# SENSE.net
KiCad netlist of a schematic drawn in Altium Designer
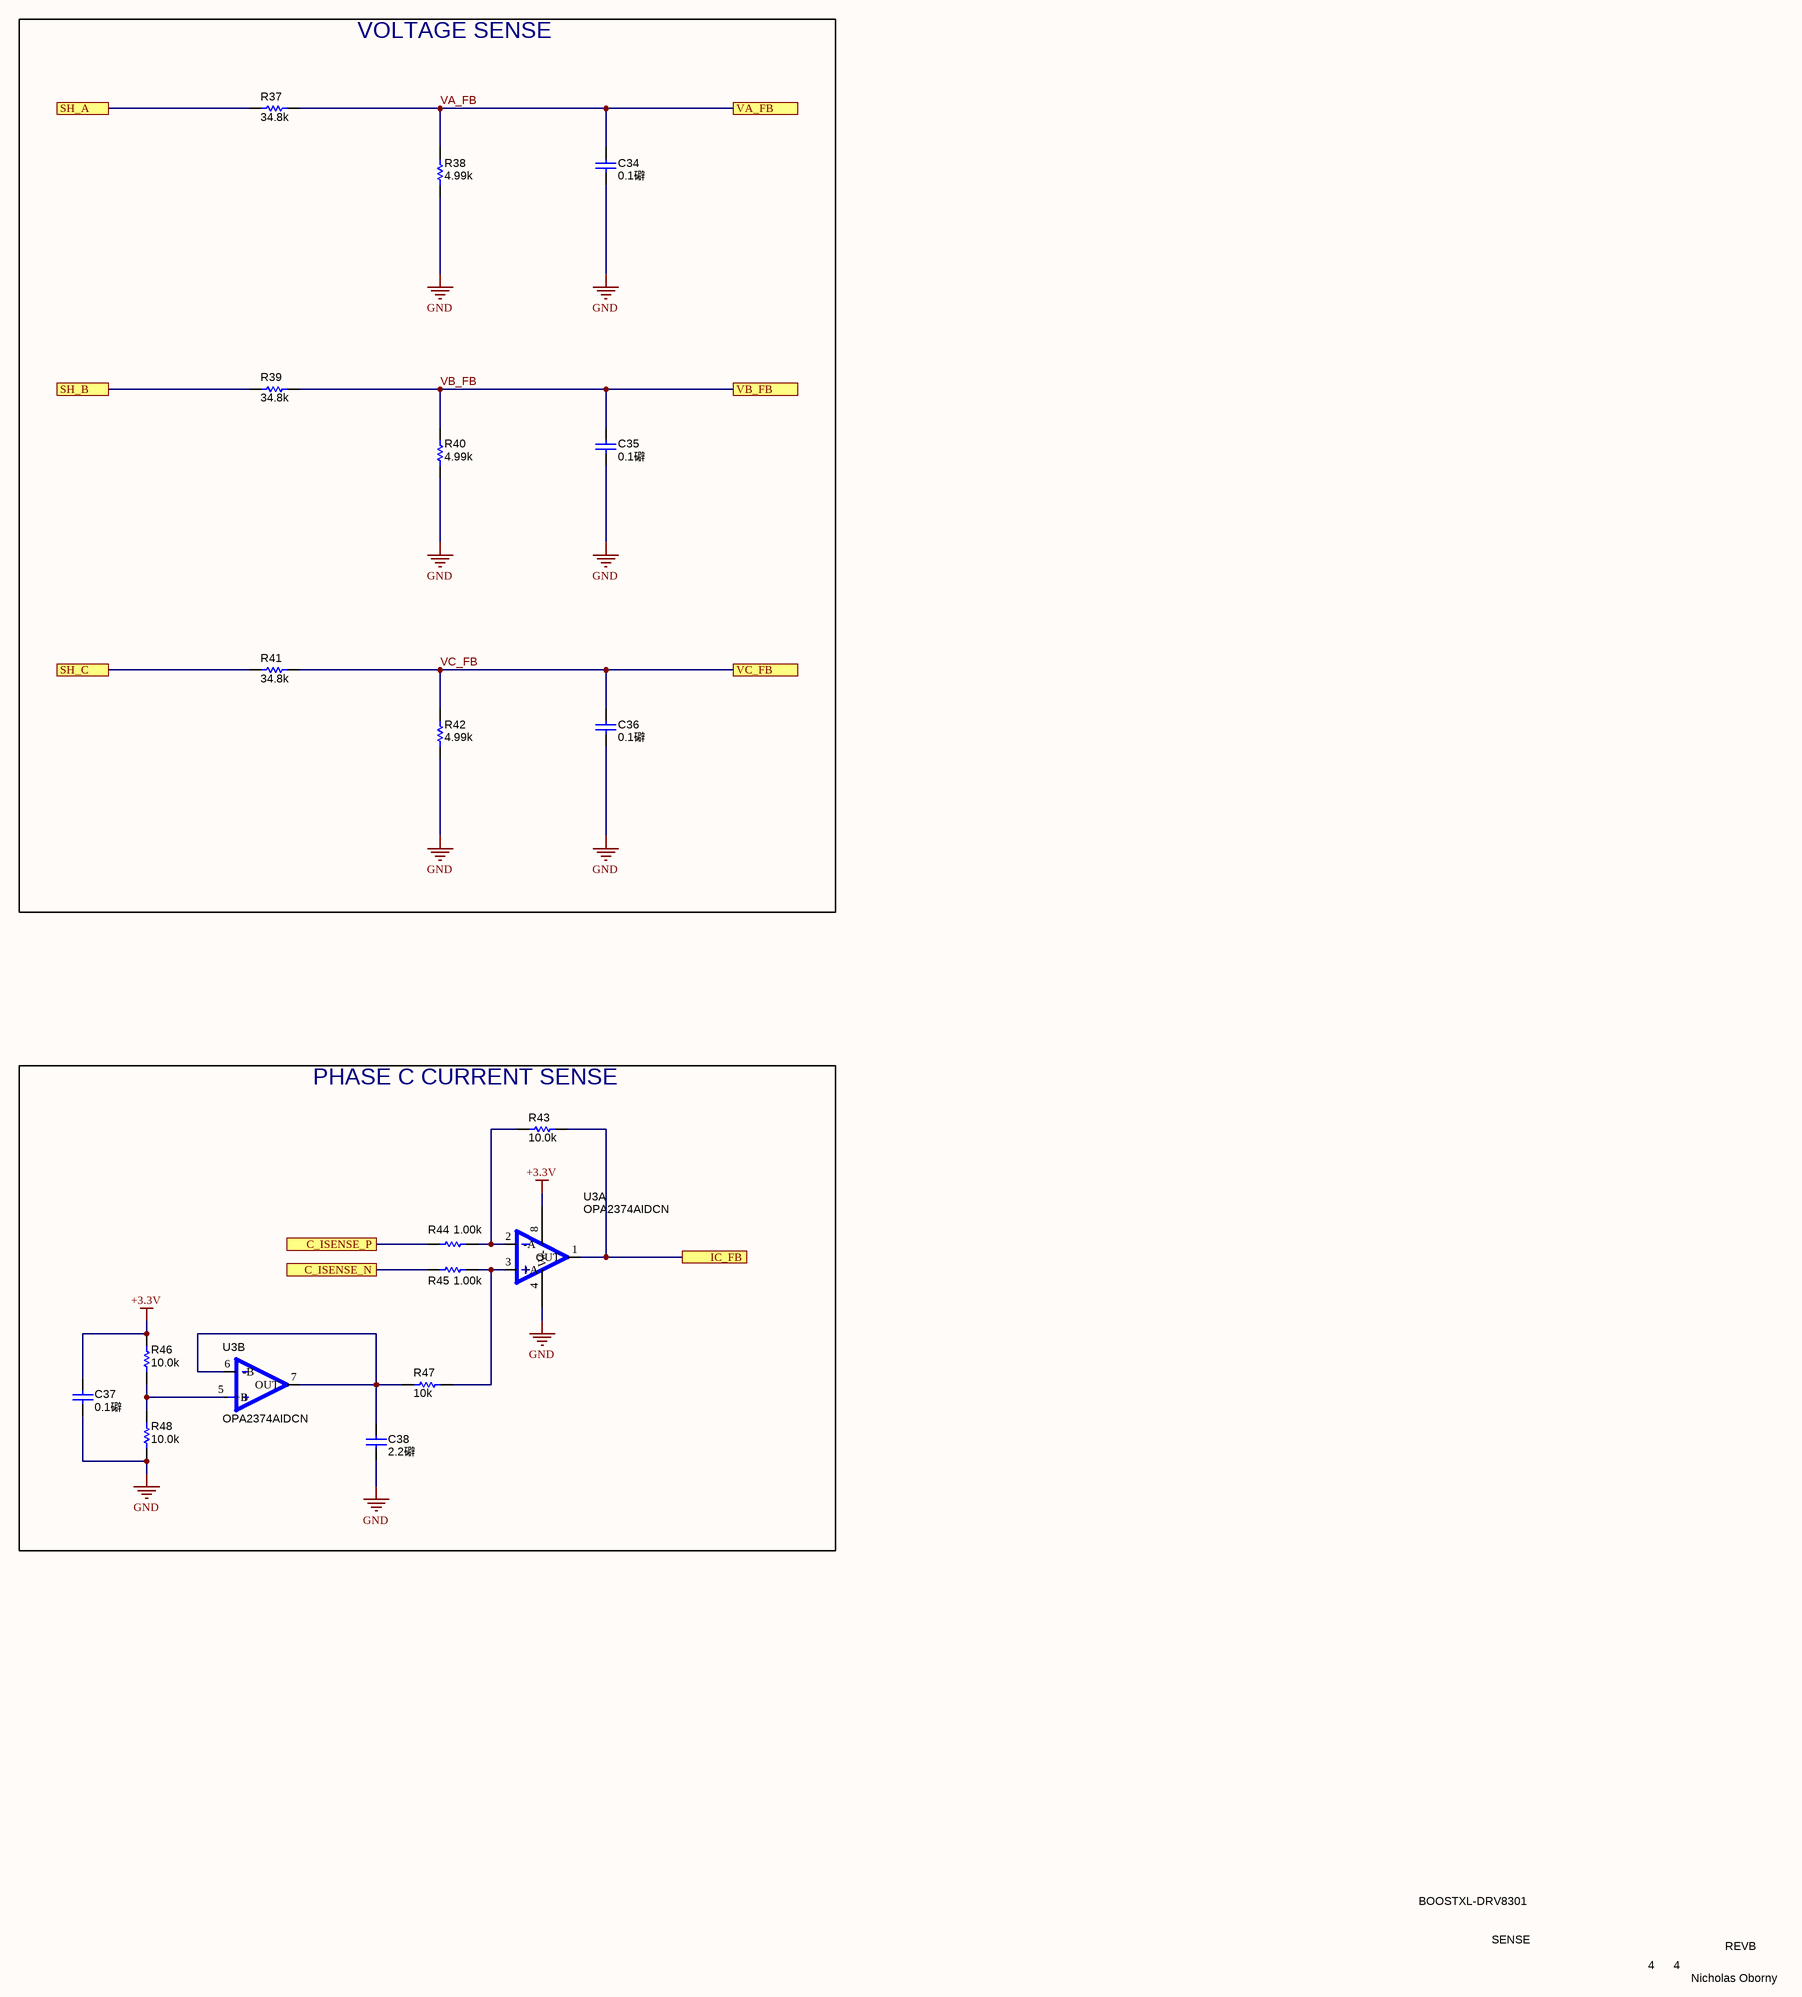
[diagram p0: SENSE.SchDoc]

(export (version "E")
  (design (tool "Eeschema 10.0.6"))
  (components
    (comp (ref "C34")
      (value "C0603C104J4RACTU")
      (footprint "0603L")
      (description "CAP, CERM, 0.1uF, 16V, +/-5%, X7R, 0603")
      (fields
        (field (name "VALUEDISPLAYED") "0.1礔")
        (field (name "MANUFACTURER") "Kemet")
        (field (name "PUBLISHER") "Texas Instruments")
      )
      (libsource (lib "Capacitor_Ceramic") (part "C0603C104J4RACTU"))
    )
    (comp (ref "C35")
      (value "C0603C104J4RACTU")
      (footprint "0603L")
      (description "CAP, CERM, 0.1uF, 16V, +/-5%, X7R, 0603")
      (fields
        (field (name "VALUEDISPLAYED") "0.1礔")
        (field (name "MANUFACTURER") "Kemet")
        (field (name "PUBLISHER") "Texas Instruments")
      )
      (libsource (lib "Capacitor_Ceramic") (part "C0603C104J4RACTU"))
    )
    (comp (ref "C36")
      (value "C0603C104J4RACTU")
      (footprint "0603L")
      (description "CAP, CERM, 0.1uF, 16V, +/-5%, X7R, 0603")
      (fields
        (field (name "VALUEDISPLAYED") "0.1礔")
        (field (name "MANUFACTURER") "Kemet")
        (field (name "PUBLISHER") "Texas Instruments")
      )
      (libsource (lib "Capacitor_Ceramic") (part "C0603C104J4RACTU"))
    )
    (comp (ref "C37")
      (value "C0603C104J4RACTU")
      (footprint "0603L")
      (description "CAP, CERM, 0.1uF, 16V, +/-5%, X7R, 0603")
      (fields
        (field (name "VALUEDISPLAYED") "0.1礔")
        (field (name "MANUFACTURER") "Kemet")
        (field (name "PUBLISHER") "Texas Instruments")
      )
      (libsource (lib "Capacitor_Ceramic") (part "C0603C104J4RACTU"))
    )
    (comp (ref "C38")
      (value "C0603C225M8PACTU")
      (footprint "0603L")
      (description "CAP, CERM, 2.2uF, 10V, +/-20%, X5R, 0603")
      (fields
        (field (name "VALUEDISPLAYED") "2.2礔")
        (field (name "MANUFACTURER") "Kemet")
        (field (name "PUBLISHER") "Texas Instruments")
      )
      (libsource (lib "Capacitor_Ceramic") (part "C0603C225M8PACTU"))
    )
    (comp (ref "R37")
      (value "34.8k")
      (footprint "0603L")
      (description "RES, 34.8k ohm, 1%, 0.1W, 0603")
      (fields
        (field (name "PARTNUMBER") "CRCW060334K8FKEA")
        (field (name "MANUFACTURER") "Vishay-Dale")
        (field (name "PUBLISHER") "Texas Instruments")
      )
      (libsource (lib "Resistor_0603") (part "CRCW060334K8FKEA"))
    )
    (comp (ref "R38")
      (value "4.99k")
      (footprint "0603L")
      (description "RES, 4.99k ohm, 1%, 0.1W, 0603")
      (fields
        (field (name "PARTNUMBER") "CRCW06034K99FKEA")
        (field (name "MANUFACTURER") "Vishay-Dale")
        (field (name "PUBLISHER") "Texas Instruments")
      )
      (libsource (lib "Resistor_0603") (part "CRCW06034K99FKEA"))
    )
    (comp (ref "R39")
      (value "34.8k")
      (footprint "0603L")
      (description "RES, 34.8k ohm, 1%, 0.1W, 0603")
      (fields
        (field (name "PARTNUMBER") "CRCW060334K8FKEA")
        (field (name "MANUFACTURER") "Vishay-Dale")
        (field (name "PUBLISHER") "Texas Instruments")
      )
      (libsource (lib "Resistor_0603") (part "CRCW060334K8FKEA"))
    )
    (comp (ref "R40")
      (value "4.99k")
      (footprint "0603L")
      (description "RES, 4.99k ohm, 1%, 0.1W, 0603")
      (fields
        (field (name "PARTNUMBER") "CRCW06034K99FKEA")
        (field (name "MANUFACTURER") "Vishay-Dale")
        (field (name "PUBLISHER") "Texas Instruments")
      )
      (libsource (lib "Resistor_0603") (part "CRCW06034K99FKEA"))
    )
    (comp (ref "R41")
      (value "34.8k")
      (footprint "0603L")
      (description "RES, 34.8k ohm, 1%, 0.1W, 0603")
      (fields
        (field (name "PARTNUMBER") "CRCW060334K8FKEA")
        (field (name "MANUFACTURER") "Vishay-Dale")
        (field (name "PUBLISHER") "Texas Instruments")
      )
      (libsource (lib "Resistor_0603") (part "CRCW060334K8FKEA"))
    )
    (comp (ref "R42")
      (value "4.99k")
      (footprint "0603L")
      (description "RES, 4.99k ohm, 1%, 0.1W, 0603")
      (fields
        (field (name "PARTNUMBER") "CRCW06034K99FKEA")
        (field (name "MANUFACTURER") "Vishay-Dale")
        (field (name "PUBLISHER") "Texas Instruments")
      )
      (libsource (lib "Resistor_0603") (part "CRCW06034K99FKEA"))
    )
    (comp (ref "R43")
      (value "10.0k")
      (footprint "0603L")
      (description "RES, 10.0k ohm, 0.1%, 0.1W, 0603")
      (fields
        (field (name "PARTNUMBER") "RG1608P-103-B-T5")
        (field (name "MANUFACTURER") "Susumu Co Ltd")
        (field (name "PUBLISHER") "Texas Instruments")
      )
      (libsource (lib "Resistor_0603") (part "RG1608P-103-B-T5"))
    )
    (comp (ref "R44")
      (value "1.00k")
      (footprint "0603L")
      (description "RES, 1.00k ohm, 1%, 0.1W, 0603")
      (fields
        (field (name "PARTNUMBER") "CRCW06031K00FKEA")
        (field (name "MANUFACTURER") "Vishay-Dale")
        (field (name "PUBLISHER") "Texas Instruments")
      )
      (libsource (lib "Resistor_0603") (part "CRCW06031K00FKEA"))
    )
    (comp (ref "R45")
      (value "1.00k")
      (footprint "0603L")
      (description "RES, 1.00k ohm, 1%, 0.1W, 0603")
      (fields
        (field (name "PARTNUMBER") "CRCW06031K00FKEA")
        (field (name "MANUFACTURER") "Vishay-Dale")
        (field (name "PUBLISHER") "Texas Instruments")
      )
      (libsource (lib "Resistor_0603") (part "CRCW06031K00FKEA"))
    )
    (comp (ref "R46")
      (value "10.0k")
      (footprint "0603L")
      (description "RES, 10.0k ohm, 0.1%, 0.1W, 0603")
      (fields
        (field (name "PARTNUMBER") "RG1608P-103-B-T5")
        (field (name "MANUFACTURER") "Susumu Co Ltd")
        (field (name "PUBLISHER") "Texas Instruments")
      )
      (libsource (lib "Resistor_0603") (part "RG1608P-103-B-T5"))
    )
    (comp (ref "R47")
      (value "10k")
      (footprint "0603L")
      (description "RES, 10k ohm, 5%, 0.1W, 0603")
      (fields
        (field (name "PARTNUMBER") "CRCW060310K0JNEA")
        (field (name "MANUFACTURER") "Vishay-Dale")
        (field (name "PUBLISHER") "Texas Instruments")
      )
      (libsource (lib "Resistor_0603") (part "CRCW060310K0JNEA"))
    )
    (comp (ref "R48")
      (value "10.0k")
      (footprint "0603L")
      (description "RES, 10.0k ohm, 0.1%, 0.1W, 0603")
      (fields
        (field (name "PARTNUMBER") "RG1608P-103-B-T5")
        (field (name "MANUFACTURER") "Susumu Co Ltd")
        (field (name "PUBLISHER") "Texas Instruments")
      )
      (libsource (lib "Resistor_0603") (part "RG1608P-103-B-T5"))
    )
    (comp (ref "U3")
      (value "OPA2374AIDCN")
      (footprint "DCN")
      (description "IC, CMOS, R-R I/O  Op Amp, Single Supply, 6.5MHz, 585uA")
      (fields (field (name "MANUFACTURER") "TI"))
      (libsource (lib "PADSlegacy_Active") (part "OPA2374AIDCN"))
    )
  )
  (nets
    (net (code "1") (name "+3.3V") (class "Default")
      (node (ref "C37") (pin "1") (pinfunction "1_1") (pintype "passive"))
      (node (ref "R46") (pin "2") (pinfunction "2_2") (pintype "passive"))
      (node (ref "U3") (pin "8") (pinfunction "V+_8") (pintype "passive"))
    )
    (net (code "2") (name "/C_ISENSE_N") (class "Default")
      (node (ref "R45") (pin "1") (pinfunction "1_1") (pintype "passive"))
    )
    (net (code "3") (name "/C_ISENSE_P") (class "Default")
      (node (ref "R44") (pin "1") (pinfunction "1_1") (pintype "passive"))
    )
    (net (code "4") (name "/IC_FB") (class "Default")
      (node (ref "R43") (pin "2") (pinfunction "2_2") (pintype "passive"))
      (node (ref "U3") (pin "1") (pinfunction "OUT_1") (pintype "passive"))
    )
    (net (code "5") (name "/SH_A") (class "Default")
      (node (ref "R37") (pin "1") (pinfunction "1_1") (pintype "passive"))
    )
    (net (code "6") (name "/SH_B") (class "Default")
      (node (ref "R39") (pin "1") (pinfunction "1_1") (pintype "passive"))
    )
    (net (code "7") (name "/SH_C") (class "Default")
      (node (ref "R41") (pin "1") (pinfunction "1_1") (pintype "passive"))
    )
    (net (code "8") (name "/VA_FB") (class "Default")
      (node (ref "C34") (pin "1") (pinfunction "1_1") (pintype "passive"))
      (node (ref "R37") (pin "2") (pinfunction "2_2") (pintype "passive"))
      (node (ref "R38") (pin "2") (pinfunction "2_2") (pintype "passive"))
    )
    (net (code "9") (name "/VB_FB") (class "Default")
      (node (ref "C35") (pin "1") (pinfunction "1_1") (pintype "passive"))
      (node (ref "R39") (pin "2") (pinfunction "2_2") (pintype "passive"))
      (node (ref "R40") (pin "2") (pinfunction "2_2") (pintype "passive"))
    )
    (net (code "10") (name "/VC_FB") (class "Default")
      (node (ref "C36") (pin "1") (pinfunction "1_1") (pintype "passive"))
      (node (ref "R41") (pin "2") (pinfunction "2_2") (pintype "passive"))
      (node (ref "R42") (pin "2") (pinfunction "2_2") (pintype "passive"))
    )
    (net (code "11") (name "GND") (class "Default")
      (node (ref "C34") (pin "2") (pinfunction "2_2") (pintype "passive"))
      (node (ref "C35") (pin "2") (pinfunction "2_2") (pintype "passive"))
      (node (ref "C36") (pin "2") (pinfunction "2_2") (pintype "passive"))
      (node (ref "C37") (pin "2") (pinfunction "2_2") (pintype "passive"))
      (node (ref "C38") (pin "2") (pinfunction "2_2") (pintype "passive"))
      (node (ref "R38") (pin "1") (pinfunction "1_1") (pintype "passive"))
      (node (ref "R40") (pin "1") (pinfunction "1_1") (pintype "passive"))
      (node (ref "R42") (pin "1") (pinfunction "1_1") (pintype "passive"))
      (node (ref "R48") (pin "1") (pinfunction "1_1") (pintype "passive"))
      (node (ref "U3") (pin "4") (pinfunction "V-_4") (pintype "passive"))
    )
    (net (code "12") (name "Net-(U3A-+A)") (class "Default")
      (node (ref "R45") (pin "2") (pinfunction "2_2") (pintype "passive"))
      (node (ref "R47") (pin "2") (pinfunction "2_2") (pintype "passive"))
      (node (ref "U3") (pin "3") (pinfunction "+A_3") (pintype "passive"))
    )
    (net (code "13") (name "Net-(U3A--A)") (class "Default")
      (node (ref "R43") (pin "1") (pinfunction "1_1") (pintype "passive"))
      (node (ref "R44") (pin "2") (pinfunction "2_2") (pintype "passive"))
      (node (ref "U3") (pin "2") (pinfunction "-A_2") (pintype "passive"))
    )
    (net (code "14") (name "Net-(U3B-+B)") (class "Default")
      (node (ref "R46") (pin "1") (pinfunction "1_1") (pintype "passive"))
      (node (ref "R48") (pin "2") (pinfunction "2_2") (pintype "passive"))
      (node (ref "U3") (pin "5") (pinfunction "+B_5") (pintype "passive"))
    )
    (net (code "15") (name "Net-(U3B--B)") (class "Default")
      (node (ref "C38") (pin "1") (pinfunction "1_1") (pintype "passive"))
      (node (ref "R47") (pin "1") (pinfunction "1_1") (pintype "passive"))
      (node (ref "U3") (pin "6") (pinfunction "-B_6") (pintype "passive"))
      (node (ref "U3") (pin "7") (pinfunction "OUT_7") (pintype "passive"))
    )
  )
)
